# OpenPixelNode.net
KiCad netlist of a schematic drawn in EAGLE
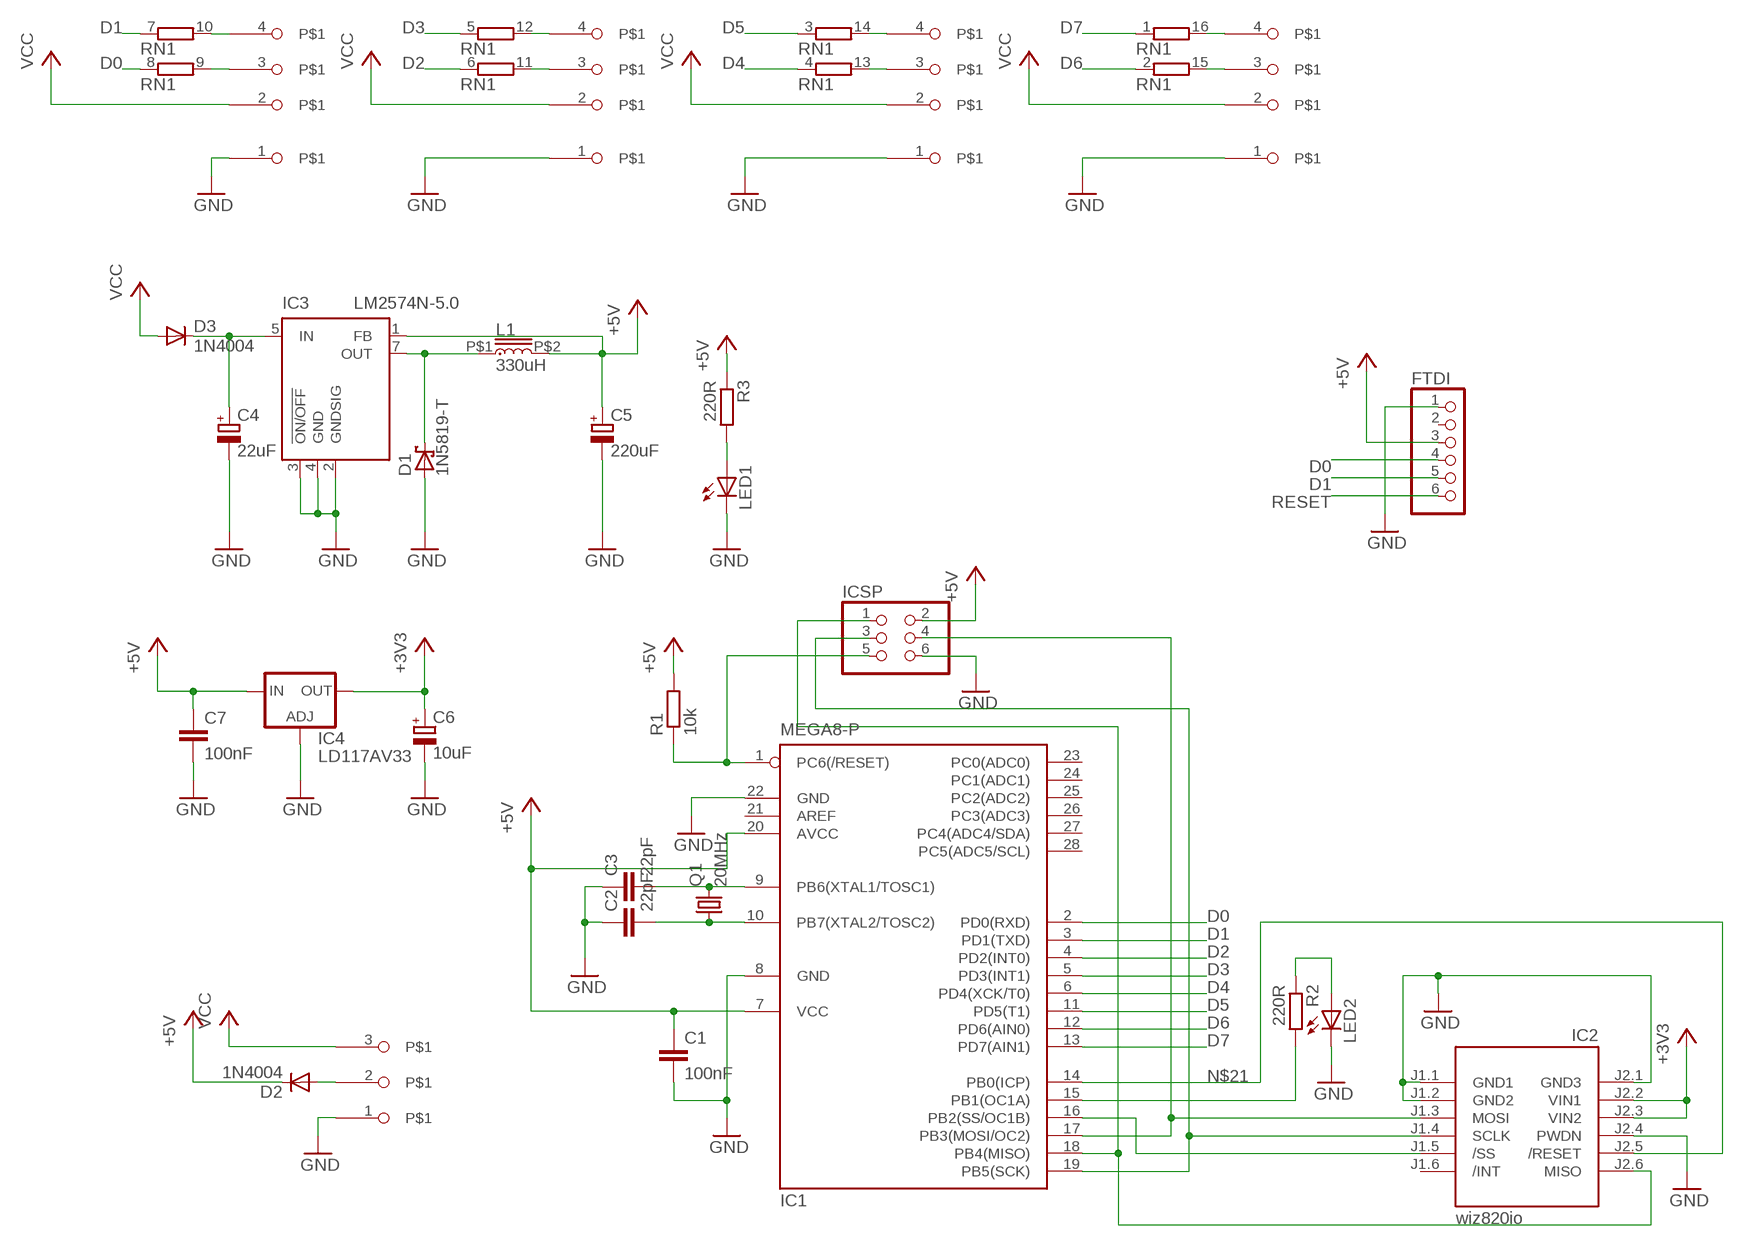
[diagram p0: schematic, sheet 1]

(export (version "E")
  (design (tool "Eeschema 10.0.6"))
  (components
    (comp (ref "C1")
      (value "100nF")
      (footprint "eagle-import:C025-025X050")
      (libsource (lib "eagle-import") (part "C-EU025-025X050"))
    )
    (comp (ref "C2")
      (value "22pF")
      (footprint "eagle-import:C025-025X050")
      (libsource (lib "eagle-import") (part "C-EU025-025X050"))
    )
    (comp (ref "C3")
      (value "22pF")
      (footprint "eagle-import:C025-025X050")
      (libsource (lib "eagle-import") (part "C-EU025-025X050"))
    )
    (comp (ref "C4")
      (value "22uF")
      (footprint "eagle-import:E2,5-6")
      (libsource (lib "eagle-import") (part "CPOL-EUE2.5-6"))
    )
    (comp (ref "C5")
      (value "220uF")
      (footprint "eagle-import:E2,5-6")
      (libsource (lib "eagle-import") (part "CPOL-EUE2.5-6"))
    )
    (comp (ref "C6")
      (value "10uF")
      (footprint "eagle-import:E2,5-6")
      (libsource (lib "eagle-import") (part "CPOL-EUE2.5-6"))
    )
    (comp (ref "C7")
      (value "100nF")
      (footprint "eagle-import:C025-025X050")
      (libsource (lib "eagle-import") (part "C-EU025-025X050"))
    )
    (comp (ref "D1")
      (value "1N5819-T")
      (footprint "eagle-import:DO41-7.6")
      (libsource (lib "eagle-import") (part "1N5819-T"))
    )
    (comp (ref "D2")
      (value "1N4004")
      (footprint "eagle-import:DO41-10")
      (libsource (lib "eagle-import") (part "1N4004"))
    )
    (comp (ref "D3")
      (value "1N4004")
      (footprint "eagle-import:DO41-10")
      (libsource (lib "eagle-import") (part "1N4004"))
    )
    (comp (ref "FTDI")
      (value "PINHD-1X6")
      (footprint "eagle-import:1X06")
      (libsource (lib "eagle-import") (part "PINHD-1X6"))
    )
    (comp (ref "IC1")
      (value "MEGA8-P")
      (footprint "eagle-import:DIL28-3")
      (libsource (lib "eagle-import") (part "MEGA8-P"))
    )
    (comp (ref "IC2")
      (value "wiz820io")
      (footprint "eagle-import:WIZ820IO")
      (libsource (lib "eagle-import") (part "WIZ820IO_DEVICE'DUAL-IN-LINE'"))
    )
    (comp (ref "IC3")
      (value "LM2574N-5.0")
      (footprint "eagle-import:DIL08")
      (libsource (lib "eagle-import") (part "LM2574?-N5.0"))
    )
    (comp (ref "IC4")
      (value "LD117AV33")
      (footprint "eagle-import:TO220L1")
      (libsource (lib "eagle-import") (part "LD117A?V33"))
    )
    (comp (ref "ICSP")
      (value "PINHD-2X3")
      (footprint "eagle-import:2X03")
      (libsource (lib "eagle-import") (part "PINHD-2X3"))
    )
    (comp (ref "L1")
      (value "330uH")
      (footprint "eagle-import:13R334C")
      (libsource (lib "eagle-import") (part "13R334C"))
    )
    (comp (ref "LED1")
      (value "LED3MM")
      (footprint "eagle-import:LED3MM")
      (libsource (lib "eagle-import") (part "LED3MM"))
    )
    (comp (ref "LED2")
      (value "LED3MM")
      (footprint "eagle-import:LED3MM")
      (libsource (lib "eagle-import") (part "LED3MM"))
    )
    (comp (ref "Q1")
      (value "20MHz")
      (footprint "eagle-import:HC49_S")
      (libsource (lib "eagle-import") (part "CRYSTALHC49S"))
    )
    (comp (ref "R1")
      (value "10k")
      (footprint "eagle-import:0207_10")
      (libsource (lib "eagle-import") (part "R-EU_0207/10"))
    )
    (comp (ref "R2")
      (value "220R")
      (footprint "eagle-import:0207_10")
      (libsource (lib "eagle-import") (part "R-EU_0207/10"))
    )
    (comp (ref "R3")
      (value "220R")
      (footprint "eagle-import:0207_10")
      (libsource (lib "eagle-import") (part "R-EU_0207/10"))
    )
    (comp (ref "RN1")
      (value "8R-P")
      (footprint "eagle-import:DIL16")
      (libsource (lib "eagle-import") (part "8R-P"))
    )
    (comp (ref "U$1")
      (value "691322110004")
      (footprint "eagle-import:691322110004")
      (libsource (lib "eagle-import") (part "691322110004"))
    )
    (comp (ref "U$2")
      (value "691322110004")
      (footprint "eagle-import:691322110004")
      (libsource (lib "eagle-import") (part "691322110004"))
    )
    (comp (ref "U$3")
      (value "691322110004")
      (footprint "eagle-import:691322110004")
      (libsource (lib "eagle-import") (part "691322110004"))
    )
    (comp (ref "U$4")
      (value "691322110004")
      (footprint "eagle-import:691322110004")
      (libsource (lib "eagle-import") (part "691322110004"))
    )
    (comp (ref "U$5")
      (value "CTB9358/3")
      (footprint "eagle-import:CTB9358_3")
      (libsource (lib "eagle-import") (part "CTB9358/3"))
    )
  )
  (nets
    (net (code "1") (name "+3V3") (class "Default")
      (node (ref "C6") (pin "+") (pinfunction "+_+") (pintype "passive"))
      (node (ref "IC2") (pin "J2.2") (pinfunction "VIN1_J2.2") (pintype "power_in"))
      (node (ref "IC2") (pin "J2.3") (pinfunction "VIN2_J2.3") (pintype "power_in"))
      (node (ref "IC4") (pin "2") (pinfunction "OUT_2") (pintype "passive"))
    )
    (net (code "2") (name "+5V") (class "Default")
      (node (ref "C1") (pin "1") (pinfunction "1_1") (pintype "passive"))
      (node (ref "C5") (pin "+") (pinfunction "+_+") (pintype "passive"))
      (node (ref "C7") (pin "1") (pinfunction "1_1") (pintype "passive"))
      (node (ref "D2") (pin "C") (pinfunction "C_C") (pintype "passive"))
      (node (ref "FTDI") (pin "3") (pinfunction "3_3") (pintype "passive"))
      (node (ref "IC1") (pin "20") (pinfunction "AVCC_20") (pintype "power_in"))
      (node (ref "IC1") (pin "7") (pinfunction "VCC_7") (pintype "power_in"))
      (node (ref "IC3") (pin "1") (pinfunction "FB_1") (pintype "input"))
      (node (ref "IC4") (pin "3") (pinfunction "IN_3") (pintype "input"))
      (node (ref "ICSP") (pin "2") (pinfunction "2_2") (pintype "passive"))
      (node (ref "L1") (pin "P$2") (pinfunction "2_P$2") (pintype "passive"))
      (node (ref "R1") (pin "2") (pinfunction "2_2") (pintype "passive"))
      (node (ref "R3") (pin "1") (pinfunction "1_1") (pintype "passive"))
    )
    (net (code "3") (name "/D0") (class "Default")
      (node (ref "FTDI") (pin "4") (pinfunction "4_4") (pintype "passive"))
      (node (ref "IC1") (pin "2") (pinfunction "PD0(RXD)_2") (pintype "bidirectional"))
      (node (ref "RN1") (pin "8") (pinfunction "1_8") (pintype "passive"))
    )
    (net (code "4") (name "/D1") (class "Default")
      (node (ref "FTDI") (pin "5") (pinfunction "5_5") (pintype "passive"))
      (node (ref "IC1") (pin "3") (pinfunction "PD1(TXD)_3") (pintype "bidirectional"))
      (node (ref "RN1") (pin "7") (pinfunction "1_7") (pintype "passive"))
    )
    (net (code "5") (name "/D2") (class "Default")
      (node (ref "IC1") (pin "4") (pinfunction "PD2(INT0)_4") (pintype "bidirectional"))
      (node (ref "RN1") (pin "6") (pinfunction "1_6") (pintype "passive"))
    )
    (net (code "6") (name "/D3") (class "Default")
      (node (ref "IC1") (pin "5") (pinfunction "PD3(INT1)_5") (pintype "bidirectional"))
      (node (ref "RN1") (pin "5") (pinfunction "1_5") (pintype "passive"))
    )
    (net (code "7") (name "/D4") (class "Default")
      (node (ref "IC1") (pin "6") (pinfunction "PD4(XCK/T0)_6") (pintype "bidirectional"))
      (node (ref "RN1") (pin "4") (pinfunction "1_4") (pintype "passive"))
    )
    (net (code "8") (name "/D5") (class "Default")
      (node (ref "IC1") (pin "11") (pinfunction "PD5(T1)_11") (pintype "bidirectional"))
      (node (ref "RN1") (pin "3") (pinfunction "1_3") (pintype "passive"))
    )
    (net (code "9") (name "/D6") (class "Default")
      (node (ref "IC1") (pin "12") (pinfunction "PD6(AIN0)_12") (pintype "bidirectional"))
      (node (ref "RN1") (pin "2") (pinfunction "1_2") (pintype "passive"))
    )
    (net (code "10") (name "/D7") (class "Default")
      (node (ref "IC1") (pin "13") (pinfunction "PD7(AIN1)_13") (pintype "bidirectional"))
      (node (ref "RN1") (pin "1") (pinfunction "1_1") (pintype "passive"))
    )
    (net (code "11") (name "/N$21") (class "Default")
      (node (ref "IC1") (pin "14") (pinfunction "PB0(ICP)_14") (pintype "bidirectional"))
      (node (ref "IC2") (pin "J2.5") (pinfunction "/RESET_J2.5") (pintype "input"))
    )
    (net (code "12") (name "/RESET") (class "Default")
      (node (ref "FTDI") (pin "6") (pinfunction "6_6") (pintype "passive"))
      (node (ref "IC1") (pin "1") (pinfunction "PC6(/RESET)_1") (pintype "bidirectional"))
      (node (ref "ICSP") (pin "5") (pinfunction "5_5") (pintype "passive"))
      (node (ref "R1") (pin "1") (pinfunction "1_1") (pintype "passive"))
    )
    (net (code "13") (name "GND") (class "Default")
      (node (ref "C1") (pin "2") (pinfunction "2_2") (pintype "passive"))
      (node (ref "C2") (pin "1") (pinfunction "1_1") (pintype "passive"))
      (node (ref "C3") (pin "1") (pinfunction "1_1") (pintype "passive"))
      (node (ref "C4") (pin "-") (pinfunction "-_-") (pintype "passive"))
      (node (ref "C5") (pin "-") (pinfunction "-_-") (pintype "passive"))
      (node (ref "C6") (pin "-") (pinfunction "-_-") (pintype "passive"))
      (node (ref "C7") (pin "2") (pinfunction "2_2") (pintype "passive"))
      (node (ref "D1") (pin "A") (pinfunction "A_A") (pintype "passive"))
      (node (ref "FTDI") (pin "1") (pinfunction "1_1") (pintype "passive"))
      (node (ref "IC1") (pin "22") (pinfunction "GND_22") (pintype "power_in"))
      (node (ref "IC1") (pin "8") (pinfunction "GND_8") (pintype "power_in"))
      (node (ref "IC2") (pin "J1.1") (pinfunction "GND1_J1.1") (pintype "power_in"))
      (node (ref "IC2") (pin "J1.2") (pinfunction "GND2_J1.2") (pintype "power_in"))
      (node (ref "IC2") (pin "J2.1") (pinfunction "GND3_J2.1") (pintype "power_in"))
      (node (ref "IC2") (pin "J2.4") (pinfunction "PWDN_J2.4") (pintype "input"))
      (node (ref "IC3") (pin "2") (pinfunction "GNDSIG_2") (pintype "input"))
      (node (ref "IC3") (pin "3") (pinfunction "~{ON/OFF}_3") (pintype "input"))
      (node (ref "IC3") (pin "4") (pinfunction "GND_4") (pintype "power_in"))
      (node (ref "IC4") (pin "1") (pinfunction "ADJ_1") (pintype "input"))
      (node (ref "ICSP") (pin "6") (pinfunction "6_6") (pintype "passive"))
      (node (ref "LED1") (pin "K") (pinfunction "C_K") (pintype "passive"))
      (node (ref "LED2") (pin "K") (pinfunction "C_K") (pintype "passive"))
      (node (ref "U$1") (pin "1") (pinfunction "P$1_1") (pintype "bidirectional"))
      (node (ref "U$2") (pin "1") (pinfunction "P$1_1") (pintype "bidirectional"))
      (node (ref "U$3") (pin "1") (pinfunction "P$1_1") (pintype "bidirectional"))
      (node (ref "U$4") (pin "1") (pinfunction "P$1_1") (pintype "bidirectional"))
      (node (ref "U$5") (pin "1") (pinfunction "P$1_1") (pintype "bidirectional"))
    )
    (net (code "14") (name "Net-(IC1-PB1(OC1A))") (class "Default")
      (node (ref "IC1") (pin "15") (pinfunction "PB1(OC1A)_15") (pintype "bidirectional"))
      (node (ref "R2") (pin "2") (pinfunction "2_2") (pintype "passive"))
    )
    (net (code "15") (name "Net-(IC1-PB2(SS{slash}OC1B))") (class "Default")
      (node (ref "IC1") (pin "16") (pinfunction "PB2(SS/OC1B)_16") (pintype "bidirectional"))
      (node (ref "IC2") (pin "J1.5") (pinfunction "/SS_J1.5") (pintype "input"))
    )
    (net (code "16") (name "Net-(IC1-PB3(MOSI{slash}OC2))") (class "Default")
      (node (ref "IC1") (pin "17") (pinfunction "PB3(MOSI/OC2)_17") (pintype "bidirectional"))
      (node (ref "IC2") (pin "J1.3") (pinfunction "MOSI_J1.3") (pintype "input"))
      (node (ref "ICSP") (pin "4") (pinfunction "4_4") (pintype "passive"))
    )
    (net (code "17") (name "Net-(IC1-PB4(MISO))") (class "Default")
      (node (ref "IC1") (pin "18") (pinfunction "PB4(MISO)_18") (pintype "bidirectional"))
      (node (ref "IC2") (pin "J2.6") (pinfunction "MISO_J2.6") (pintype "output"))
      (node (ref "ICSP") (pin "1") (pinfunction "1_1") (pintype "passive"))
    )
    (net (code "18") (name "Net-(IC1-PB5(SCK))") (class "Default")
      (node (ref "IC1") (pin "19") (pinfunction "PB5(SCK)_19") (pintype "bidirectional"))
      (node (ref "IC2") (pin "J1.4") (pinfunction "SCLK_J1.4") (pintype "input"))
      (node (ref "ICSP") (pin "3") (pinfunction "3_3") (pintype "passive"))
    )
    (net (code "19") (name "Net-(IC1-PB6(XTAL1{slash}TOSC1))") (class "Default")
      (node (ref "C3") (pin "2") (pinfunction "2_2") (pintype "passive"))
      (node (ref "IC1") (pin "9") (pinfunction "PB6(XTAL1/TOSC1)_9") (pintype "bidirectional"))
      (node (ref "Q1") (pin "2") (pinfunction "2_2") (pintype "passive"))
    )
    (net (code "20") (name "Net-(IC1-PB7(XTAL2{slash}TOSC2))") (class "Default")
      (node (ref "C2") (pin "2") (pinfunction "2_2") (pintype "passive"))
      (node (ref "IC1") (pin "10") (pinfunction "PB7(XTAL2/TOSC2)_10") (pintype "bidirectional"))
      (node (ref "Q1") (pin "1") (pinfunction "1_1") (pintype "passive"))
    )
    (net (code "21") (name "Net-(IC3-IN)") (class "Default")
      (node (ref "C4") (pin "+") (pinfunction "+_+") (pintype "passive"))
      (node (ref "D3") (pin "C") (pinfunction "C_C") (pintype "passive"))
      (node (ref "IC3") (pin "5") (pinfunction "IN_5") (pintype "input"))
    )
    (net (code "22") (name "Net-(IC3-OUT)") (class "Default")
      (node (ref "D1") (pin "C") (pinfunction "C_C") (pintype "passive"))
      (node (ref "IC3") (pin "7") (pinfunction "OUT_7") (pintype "passive"))
      (node (ref "L1") (pin "P$1") (pinfunction "1_P$1") (pintype "passive"))
    )
    (net (code "23") (name "Net-(LED1-PadA)") (class "Default")
      (node (ref "LED1") (pin "A") (pinfunction "A_A") (pintype "passive"))
      (node (ref "R3") (pin "2") (pinfunction "2_2") (pintype "passive"))
    )
    (net (code "24") (name "Net-(LED2-PadA)") (class "Default")
      (node (ref "LED2") (pin "A") (pinfunction "A_A") (pintype "passive"))
      (node (ref "R2") (pin "1") (pinfunction "1_1") (pintype "passive"))
    )
    (net (code "25") (name "Net-(RN1A-2)") (class "Default")
      (node (ref "RN1") (pin "16") (pinfunction "2_16") (pintype "passive"))
      (node (ref "U$4") (pin "4") (pinfunction "P$1_4") (pintype "bidirectional"))
    )
    (net (code "26") (name "Net-(RN1B-2)") (class "Default")
      (node (ref "RN1") (pin "15") (pinfunction "2_15") (pintype "passive"))
      (node (ref "U$4") (pin "3") (pinfunction "P$1_3") (pintype "bidirectional"))
    )
    (net (code "27") (name "Net-(RN1C-2)") (class "Default")
      (node (ref "RN1") (pin "14") (pinfunction "2_14") (pintype "passive"))
      (node (ref "U$3") (pin "4") (pinfunction "P$1_4") (pintype "bidirectional"))
    )
    (net (code "28") (name "Net-(RN1D-2)") (class "Default")
      (node (ref "RN1") (pin "13") (pinfunction "2_13") (pintype "passive"))
      (node (ref "U$3") (pin "3") (pinfunction "P$1_3") (pintype "bidirectional"))
    )
    (net (code "29") (name "Net-(RN1E-2)") (class "Default")
      (node (ref "RN1") (pin "12") (pinfunction "2_12") (pintype "passive"))
      (node (ref "U$2") (pin "4") (pinfunction "P$1_4") (pintype "bidirectional"))
    )
    (net (code "30") (name "Net-(RN1F-2)") (class "Default")
      (node (ref "RN1") (pin "11") (pinfunction "2_11") (pintype "passive"))
      (node (ref "U$2") (pin "3") (pinfunction "P$1_3") (pintype "bidirectional"))
    )
    (net (code "31") (name "Net-(RN1G-2)") (class "Default")
      (node (ref "RN1") (pin "10") (pinfunction "2_10") (pintype "passive"))
      (node (ref "U$1") (pin "4") (pinfunction "P$1_4") (pintype "bidirectional"))
    )
    (net (code "32") (name "Net-(RN1H-2)") (class "Default")
      (node (ref "RN1") (pin "9") (pinfunction "2_9") (pintype "passive"))
      (node (ref "U$1") (pin "3") (pinfunction "P$1_3") (pintype "bidirectional"))
    )
    (net (code "33") (name "Net-(U$5B-P$1)") (class "Default")
      (node (ref "D2") (pin "A") (pinfunction "A_A") (pintype "passive"))
      (node (ref "U$5") (pin "2") (pinfunction "P$1_2") (pintype "bidirectional"))
    )
    (net (code "34") (name "VCC") (class "Default")
      (node (ref "D3") (pin "A") (pinfunction "A_A") (pintype "passive"))
      (node (ref "U$1") (pin "2") (pinfunction "P$1_2") (pintype "bidirectional"))
      (node (ref "U$2") (pin "2") (pinfunction "P$1_2") (pintype "bidirectional"))
      (node (ref "U$3") (pin "2") (pinfunction "P$1_2") (pintype "bidirectional"))
      (node (ref "U$4") (pin "2") (pinfunction "P$1_2") (pintype "bidirectional"))
      (node (ref "U$5") (pin "3") (pinfunction "P$1_3") (pintype "bidirectional"))
    )
    (net (code "35") (name "unconnected-(FTDI-Pad2)") (class "Default")
      (node (ref "FTDI") (pin "2") (pinfunction "2_2") (pintype "passive"))
    )
    (net (code "36") (name "unconnected-(IC1-AREF-Pad21)") (class "Default")
      (node (ref "IC1") (pin "21") (pinfunction "AREF_21") (pintype "passive"))
    )
    (net (code "37") (name "unconnected-(IC1-PC0(ADC0)-Pad23)") (class "Default")
      (node (ref "IC1") (pin "23") (pinfunction "PC0(ADC0)_23") (pintype "bidirectional"))
    )
    (net (code "38") (name "unconnected-(IC1-PC1(ADC1)-Pad24)") (class "Default")
      (node (ref "IC1") (pin "24") (pinfunction "PC1(ADC1)_24") (pintype "bidirectional"))
    )
    (net (code "39") (name "unconnected-(IC1-PC2(ADC2)-Pad25)") (class "Default")
      (node (ref "IC1") (pin "25") (pinfunction "PC2(ADC2)_25") (pintype "bidirectional"))
    )
    (net (code "40") (name "unconnected-(IC1-PC3(ADC3)-Pad26)") (class "Default")
      (node (ref "IC1") (pin "26") (pinfunction "PC3(ADC3)_26") (pintype "bidirectional"))
    )
    (net (code "41") (name "unconnected-(IC1-PC4(ADC4{slash}SDA)-Pad27)") (class "Default")
      (node (ref "IC1") (pin "27") (pinfunction "PC4(ADC4/SDA)_27") (pintype "bidirectional"))
    )
    (net (code "42") (name "unconnected-(IC1-PC5(ADC5{slash}SCL)-Pad28)") (class "Default")
      (node (ref "IC1") (pin "28") (pinfunction "PC5(ADC5/SCL)_28") (pintype "bidirectional"))
    )
    (net (code "43") (name "unconnected-(IC2-{slash}INT-PadJ1.6)") (class "Default")
      (node (ref "IC2") (pin "J1.6") (pinfunction "/INT_J1.6") (pintype "output"))
    )
  )
)
